# CabInst.net
KiCad netlist of a schematic drawn in EAGLE
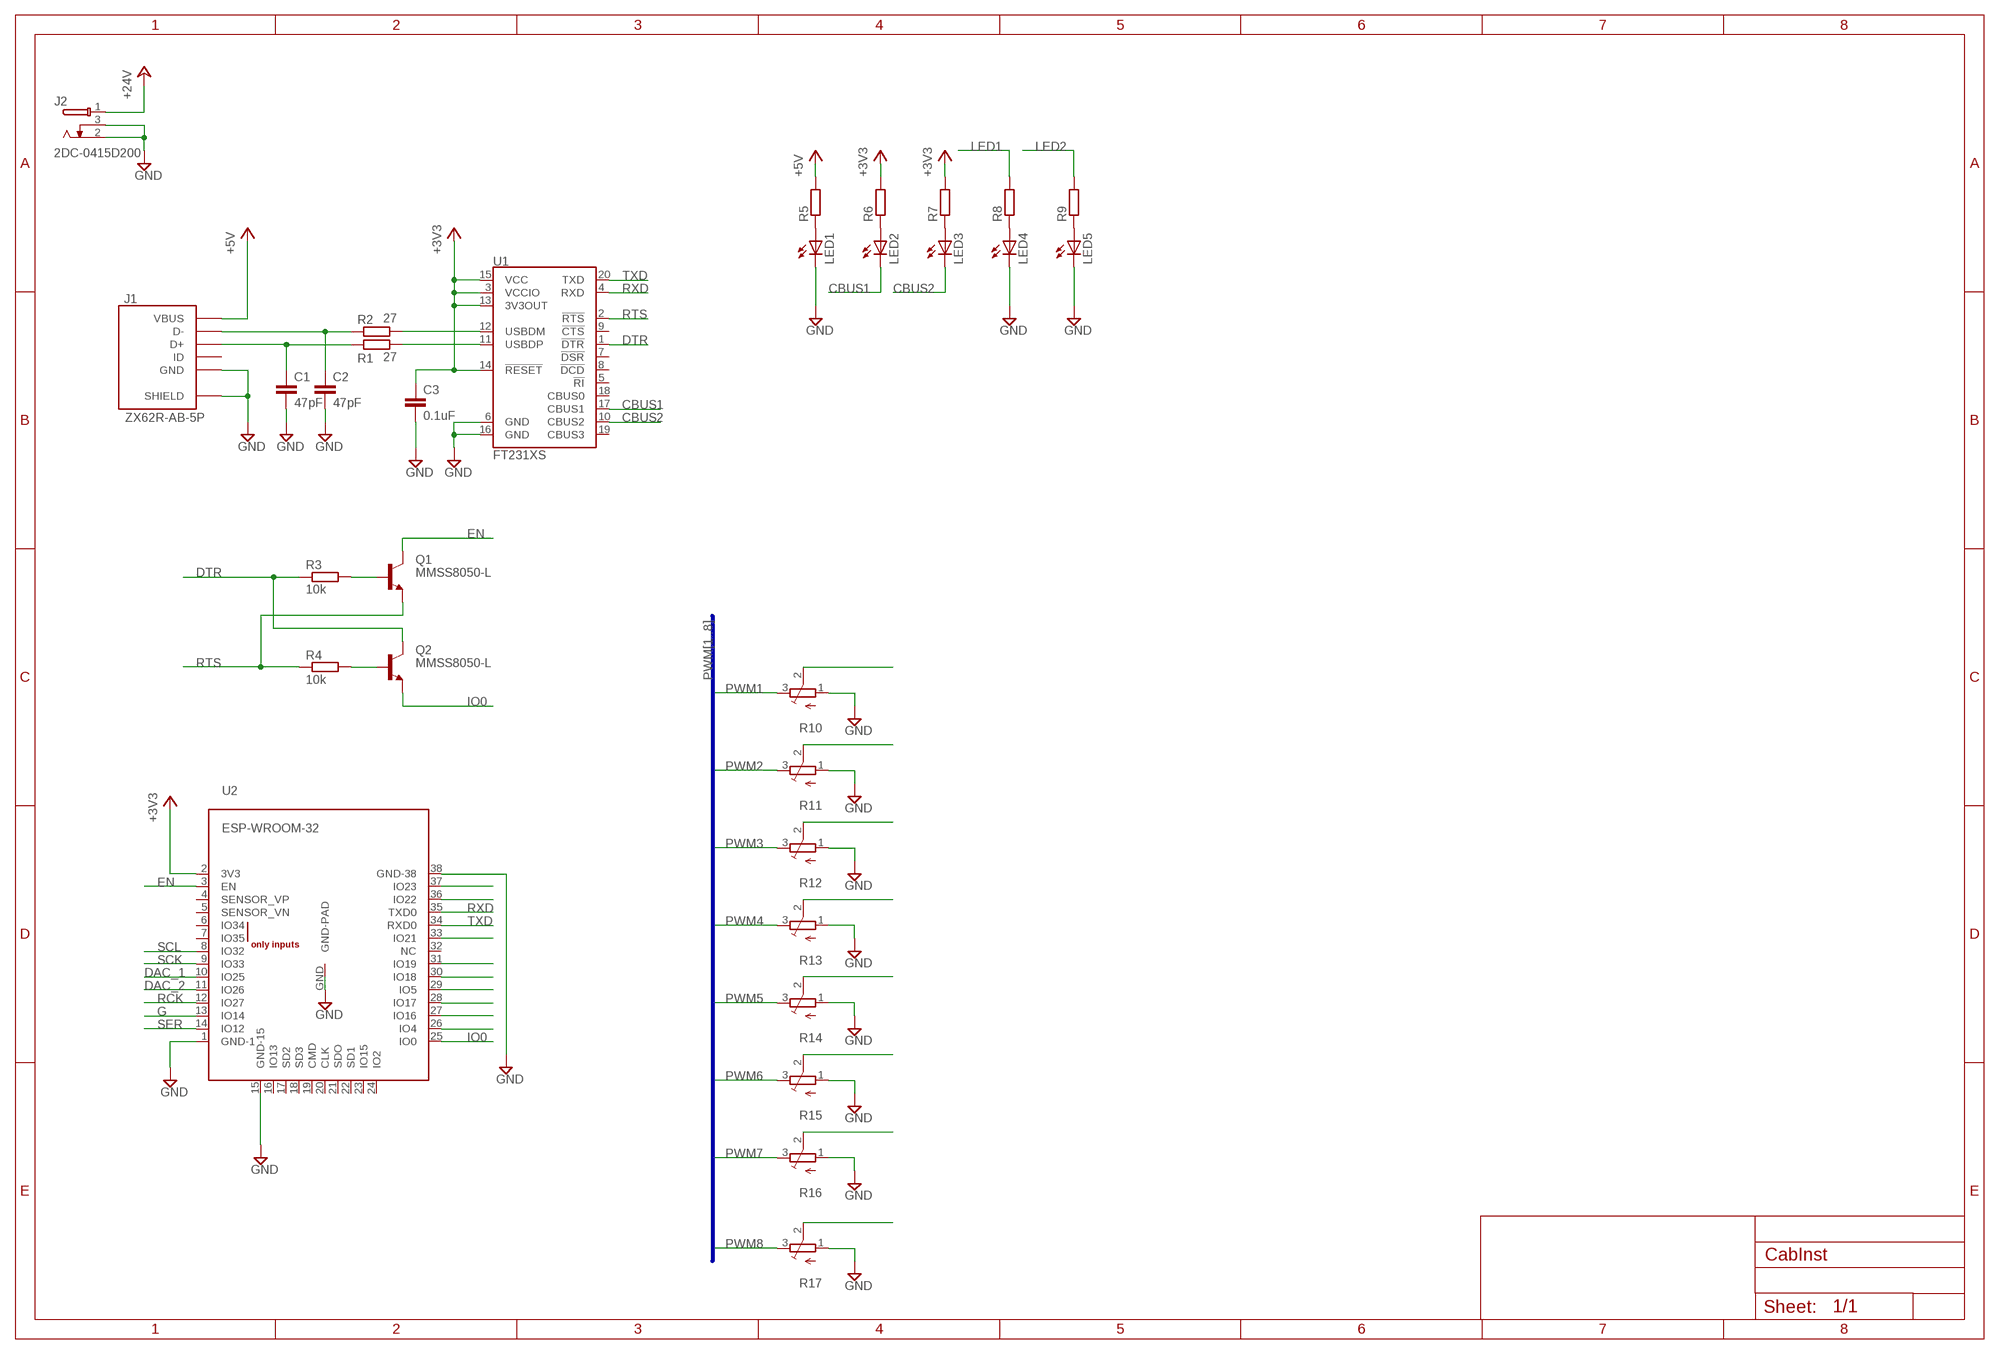
[diagram p0: schematic, sheet 1]

(export (version "E")
  (design (tool "Eeschema 10.0.6"))
  (components
    (comp (ref "C1")
      (value "47pF")
      (footprint "eagle-import:C0603")
      (libsource (lib "eagle-import") (part "C-EUC0603"))
    )
    (comp (ref "C2")
      (value "47pF")
      (footprint "eagle-import:C0603")
      (libsource (lib "eagle-import") (part "C-EUC0603"))
    )
    (comp (ref "C3")
      (value "0.1uF")
      (footprint "eagle-import:C0603")
      (libsource (lib "eagle-import") (part "C-EUC0603"))
    )
    (comp (ref "J1")
      (value "ZX62R-AB-5P")
      (footprint "eagle-import:ZX62R-B-5PA")
      (libsource (lib "eagle-import") (part "ZX62R-AB-5P"))
    )
    (comp (ref "J2")
      (value "2DC-0415D200")
      (footprint "eagle-import:2DC-0415D200")
      (libsource (lib "eagle-import") (part "2DC-0415D200"))
    )
    (comp (ref "LED1")
      (value "LEDCHIP-LED0603")
      (footprint "eagle-import:CHIP-LED0603")
      (libsource (lib "eagle-import") (part "LEDCHIP-LED0603"))
    )
    (comp (ref "LED2")
      (value "LEDCHIP-LED0603")
      (footprint "eagle-import:CHIP-LED0603")
      (libsource (lib "eagle-import") (part "LEDCHIP-LED0603"))
    )
    (comp (ref "LED3")
      (value "LEDCHIP-LED0603")
      (footprint "eagle-import:CHIP-LED0603")
      (libsource (lib "eagle-import") (part "LEDCHIP-LED0603"))
    )
    (comp (ref "LED4")
      (value "LEDCHIP-LED0603")
      (footprint "eagle-import:CHIP-LED0603")
      (libsource (lib "eagle-import") (part "LEDCHIP-LED0603"))
    )
    (comp (ref "LED5")
      (value "LEDCHIP-LED0603")
      (footprint "eagle-import:CHIP-LED0603")
      (libsource (lib "eagle-import") (part "LEDCHIP-LED0603"))
    )
    (comp (ref "Q1")
      (value "MMSS8050-L")
      (footprint "eagle-import:SOT23")
      (libsource (lib "eagle-import") (part "MMSS8050-L"))
    )
    (comp (ref "Q2")
      (value "MMSS8050-L")
      (footprint "eagle-import:SOT23")
      (libsource (lib "eagle-import") (part "MMSS8050-L"))
    )
    (comp (ref "R1")
      (value "27")
      (footprint "eagle-import:R0603")
      (libsource (lib "eagle-import") (part "R-EU_R0603"))
    )
    (comp (ref "R2")
      (value "27")
      (footprint "eagle-import:R0603")
      (libsource (lib "eagle-import") (part "R-EU_R0603"))
    )
    (comp (ref "R3")
      (value "10k")
      (footprint "eagle-import:R0603")
      (libsource (lib "eagle-import") (part "R-EU_R0603"))
    )
    (comp (ref "R4")
      (value "10k")
      (footprint "eagle-import:R0603")
      (libsource (lib "eagle-import") (part "R-EU_R0603"))
    )
    (comp (ref "R5")
      (value "R-EU_R0603")
      (footprint "eagle-import:R0603")
      (libsource (lib "eagle-import") (part "R-EU_R0603"))
    )
    (comp (ref "R6")
      (value "R-EU_R0603")
      (footprint "eagle-import:R0603")
      (libsource (lib "eagle-import") (part "R-EU_R0603"))
    )
    (comp (ref "R7")
      (value "R-EU_R0603")
      (footprint "eagle-import:R0603")
      (libsource (lib "eagle-import") (part "R-EU_R0603"))
    )
    (comp (ref "R8")
      (value "R-EU_R0603")
      (footprint "eagle-import:R0603")
      (libsource (lib "eagle-import") (part "R-EU_R0603"))
    )
    (comp (ref "R9")
      (value "R-EU_R0603")
      (footprint "eagle-import:R0603")
      (libsource (lib "eagle-import") (part "R-EU_R0603"))
    )
    (comp (ref "R10")
      (value "TRIM_EU-SM-42/43A")
      (footprint "eagle-import:SM-42_43A")
      (libsource (lib "eagle-import") (part "TRIM_EU-SM-42/43A"))
    )
    (comp (ref "R11")
      (value "TRIM_EU-SM-42/43A")
      (footprint "eagle-import:SM-42_43A")
      (libsource (lib "eagle-import") (part "TRIM_EU-SM-42/43A"))
    )
    (comp (ref "R12")
      (value "TRIM_EU-SM-42/43A")
      (footprint "eagle-import:SM-42_43A")
      (libsource (lib "eagle-import") (part "TRIM_EU-SM-42/43A"))
    )
    (comp (ref "R13")
      (value "TRIM_EU-SM-42/43A")
      (footprint "eagle-import:SM-42_43A")
      (libsource (lib "eagle-import") (part "TRIM_EU-SM-42/43A"))
    )
    (comp (ref "R14")
      (value "TRIM_EU-SM-42/43A")
      (footprint "eagle-import:SM-42_43A")
      (libsource (lib "eagle-import") (part "TRIM_EU-SM-42/43A"))
    )
    (comp (ref "R15")
      (value "TRIM_EU-SM-42/43A")
      (footprint "eagle-import:SM-42_43A")
      (libsource (lib "eagle-import") (part "TRIM_EU-SM-42/43A"))
    )
    (comp (ref "R16")
      (value "TRIM_EU-SM-42/43A")
      (footprint "eagle-import:SM-42_43A")
      (libsource (lib "eagle-import") (part "TRIM_EU-SM-42/43A"))
    )
    (comp (ref "R17")
      (value "TRIM_EU-SM-42/43A")
      (footprint "eagle-import:SM-42_43A")
      (libsource (lib "eagle-import") (part "TRIM_EU-SM-42/43A"))
    )
    (comp (ref "U1")
      (value "FT231XS")
      (footprint "eagle-import:SSOP20_L")
      (libsource (lib "eagle-import") (part "FT231XS"))
    )
    (comp (ref "U2")
      (value "ESP-WROOM-32")
      (footprint "eagle-import:ESP-WROOM-32")
      (libsource (lib "eagle-import") (part "ESP-WROOM-32"))
    )
  )
  (nets
    (net (code "1") (name "+3V3") (class "Default")
      (node (ref "C3") (pin "1") (pinfunction "1_1") (pintype "passive"))
      (node (ref "R6") (pin "2") (pinfunction "2_2") (pintype "passive"))
      (node (ref "R7") (pin "2") (pinfunction "2_2") (pintype "passive"))
      (node (ref "U1") (pin "13") (pinfunction "3V3OUT_13") (pintype "bidirectional"))
      (node (ref "U1") (pin "14") (pinfunction "~{RESET}_14") (pintype "bidirectional"))
      (node (ref "U1") (pin "15") (pinfunction "VCC_15") (pintype "bidirectional"))
      (node (ref "U1") (pin "3") (pinfunction "VCCIO_3") (pintype "bidirectional"))
      (node (ref "U2") (pin "2") (pinfunction "3V3_2") (pintype "bidirectional"))
    )
    (net (code "2") (name "+5V") (class "Default")
      (node (ref "J1") (pin "VCC") (pinfunction "VBUS_VCC") (pintype "bidirectional"))
      (node (ref "R5") (pin "2") (pinfunction "2_2") (pintype "passive"))
    )
    (net (code "3") (name "+24V") (class "Default")
      (node (ref "J2") (pin "1") (pinfunction "1_1") (pintype "passive"))
    )
    (net (code "4") (name "/CBUS1") (class "Default")
      (node (ref "LED2") (pin "C") (pinfunction "C_C") (pintype "passive"))
      (node (ref "U1") (pin "17") (pinfunction "CBUS1_17") (pintype "bidirectional"))
    )
    (net (code "5") (name "/CBUS2") (class "Default")
      (node (ref "LED3") (pin "C") (pinfunction "C_C") (pintype "passive"))
      (node (ref "U1") (pin "10") (pinfunction "CBUS2_10") (pintype "bidirectional"))
    )
    (net (code "6") (name "/DAC_1") (class "Default")
      (node (ref "U2") (pin "10") (pinfunction "IO25_10") (pintype "bidirectional"))
    )
    (net (code "7") (name "/DAC_2") (class "Default")
      (node (ref "U2") (pin "11") (pinfunction "IO26_11") (pintype "bidirectional"))
    )
    (net (code "8") (name "/DTR") (class "Default")
      (node (ref "Q2") (pin "C") (pinfunction "C_C") (pintype "passive"))
      (node (ref "R3") (pin "1") (pinfunction "1_1") (pintype "passive"))
      (node (ref "U1") (pin "1") (pinfunction "~{DTR}_1") (pintype "bidirectional"))
    )
    (net (code "9") (name "/EN") (class "Default")
      (node (ref "Q1") (pin "C") (pinfunction "C_C") (pintype "passive"))
      (node (ref "U2") (pin "3") (pinfunction "EN_3") (pintype "bidirectional"))
    )
    (net (code "10") (name "/G") (class "Default")
      (node (ref "U2") (pin "13") (pinfunction "IO14_13") (pintype "bidirectional"))
    )
    (net (code "11") (name "/IO0") (class "Default")
      (node (ref "Q2") (pin "E") (pinfunction "E_E") (pintype "passive"))
      (node (ref "U2") (pin "25") (pinfunction "IO0_25") (pintype "bidirectional"))
    )
    (net (code "12") (name "/LED1") (class "Default")
      (node (ref "R8") (pin "2") (pinfunction "2_2") (pintype "passive"))
    )
    (net (code "13") (name "/LED2") (class "Default")
      (node (ref "R9") (pin "2") (pinfunction "2_2") (pintype "passive"))
    )
    (net (code "14") (name "/PWM1") (class "Default")
      (node (ref "R10") (pin "3") (pinfunction "E_3") (pintype "passive"))
    )
    (net (code "15") (name "/PWM2") (class "Default")
      (node (ref "R11") (pin "3") (pinfunction "E_3") (pintype "passive"))
    )
    (net (code "16") (name "/PWM3") (class "Default")
      (node (ref "R12") (pin "3") (pinfunction "E_3") (pintype "passive"))
    )
    (net (code "17") (name "/PWM4") (class "Default")
      (node (ref "R13") (pin "3") (pinfunction "E_3") (pintype "passive"))
    )
    (net (code "18") (name "/PWM5") (class "Default")
      (node (ref "R14") (pin "3") (pinfunction "E_3") (pintype "passive"))
    )
    (net (code "19") (name "/PWM6") (class "Default")
      (node (ref "R15") (pin "3") (pinfunction "E_3") (pintype "passive"))
    )
    (net (code "20") (name "/PWM7") (class "Default")
      (node (ref "R16") (pin "3") (pinfunction "E_3") (pintype "passive"))
    )
    (net (code "21") (name "/PWM8") (class "Default")
      (node (ref "R17") (pin "3") (pinfunction "E_3") (pintype "passive"))
    )
    (net (code "23") (name "/RCK") (class "Default")
      (node (ref "U2") (pin "12") (pinfunction "IO27_12") (pintype "bidirectional"))
    )
    (net (code "24") (name "/RTS") (class "Default")
      (node (ref "Q1") (pin "E") (pinfunction "E_E") (pintype "passive"))
      (node (ref "R4") (pin "1") (pinfunction "1_1") (pintype "passive"))
      (node (ref "U1") (pin "2") (pinfunction "~{RTS}_2") (pintype "bidirectional"))
    )
    (net (code "25") (name "/RXD") (class "Default")
      (node (ref "U1") (pin "4") (pinfunction "RXD_4") (pintype "bidirectional"))
      (node (ref "U2") (pin "35") (pinfunction "TXD0_35") (pintype "bidirectional"))
    )
    (net (code "26") (name "/SCK") (class "Default")
      (node (ref "U2") (pin "9") (pinfunction "IO33_9") (pintype "bidirectional"))
    )
    (net (code "27") (name "/SCL") (class "Default")
      (node (ref "U2") (pin "8") (pinfunction "IO32_8") (pintype "bidirectional"))
    )
    (net (code "28") (name "/SER") (class "Default")
      (node (ref "U2") (pin "14") (pinfunction "IO12_14") (pintype "bidirectional"))
    )
    (net (code "29") (name "/TXD") (class "Default")
      (node (ref "U1") (pin "20") (pinfunction "TXD_20") (pintype "bidirectional"))
      (node (ref "U2") (pin "34") (pinfunction "RXD0_34") (pintype "bidirectional"))
    )
    (net (code "30") (name "GND") (class "Default")
      (node (ref "C1") (pin "2") (pinfunction "2_2") (pintype "passive"))
      (node (ref "C2") (pin "2") (pinfunction "2_2") (pintype "passive"))
      (node (ref "C3") (pin "2") (pinfunction "2_2") (pintype "passive"))
      (node (ref "J1") (pin "GND") (pinfunction "GND_GND") (pintype "bidirectional"))
      (node (ref "J1") (pin "SHIELD@1") (pinfunction "SHIELD_SHIELD@1") (pintype "bidirectional"))
      (node (ref "J1") (pin "SHIELD@2") (pinfunction "SHIELD_SHIELD@2") (pintype "bidirectional"))
      (node (ref "J1") (pin "SHIELD@3") (pinfunction "SHIELD_SHIELD@3") (pintype "bidirectional"))
      (node (ref "J1") (pin "SHIELD@4") (pinfunction "SHIELD_SHIELD@4") (pintype "bidirectional"))
      (node (ref "J2") (pin "2") (pinfunction "2_2") (pintype "passive"))
      (node (ref "J2") (pin "3") (pinfunction "3_3") (pintype "passive"))
      (node (ref "LED1") (pin "C") (pinfunction "C_C") (pintype "passive"))
      (node (ref "LED4") (pin "C") (pinfunction "C_C") (pintype "passive"))
      (node (ref "LED5") (pin "C") (pinfunction "C_C") (pintype "passive"))
      (node (ref "R10") (pin "1") (pinfunction "A_1") (pintype "passive"))
      (node (ref "R11") (pin "1") (pinfunction "A_1") (pintype "passive"))
      (node (ref "R12") (pin "1") (pinfunction "A_1") (pintype "passive"))
      (node (ref "R13") (pin "1") (pinfunction "A_1") (pintype "passive"))
      (node (ref "R14") (pin "1") (pinfunction "A_1") (pintype "passive"))
      (node (ref "R15") (pin "1") (pinfunction "A_1") (pintype "passive"))
      (node (ref "R16") (pin "1") (pinfunction "A_1") (pintype "passive"))
      (node (ref "R17") (pin "1") (pinfunction "A_1") (pintype "passive"))
      (node (ref "U1") (pin "16") (pinfunction "GND_16") (pintype "bidirectional"))
      (node (ref "U1") (pin "6") (pinfunction "GND_6") (pintype "bidirectional"))
      (node (ref "U2") (pin "1") (pinfunction "GND-1_1") (pintype "bidirectional"))
      (node (ref "U2") (pin "15") (pinfunction "GND-15_15") (pintype "bidirectional"))
      (node (ref "U2") (pin "38") (pinfunction "GND-38_38") (pintype "bidirectional"))
      (node (ref "U2") (pin "GND") (pinfunction "GND-PAD_GND") (pintype "bidirectional"))
    )
    (net (code "31") (name "Net-(C1-Pad1)") (class "Default")
      (node (ref "C1") (pin "1") (pinfunction "1_1") (pintype "passive"))
      (node (ref "J1") (pin "D+") (pinfunction "D+_D+") (pintype "bidirectional"))
      (node (ref "R1") (pin "1") (pinfunction "1_1") (pintype "passive"))
    )
    (net (code "32") (name "Net-(C2-Pad1)") (class "Default")
      (node (ref "C2") (pin "1") (pinfunction "1_1") (pintype "passive"))
      (node (ref "J1") (pin "D-") (pinfunction "D-_D-") (pintype "bidirectional"))
      (node (ref "R2") (pin "1") (pinfunction "1_1") (pintype "passive"))
    )
    (net (code "33") (name "Net-(LED1-PadA)") (class "Default")
      (node (ref "LED1") (pin "A") (pinfunction "A_A") (pintype "passive"))
      (node (ref "R5") (pin "1") (pinfunction "1_1") (pintype "passive"))
    )
    (net (code "34") (name "Net-(LED2-PadA)") (class "Default")
      (node (ref "LED2") (pin "A") (pinfunction "A_A") (pintype "passive"))
      (node (ref "R6") (pin "1") (pinfunction "1_1") (pintype "passive"))
    )
    (net (code "35") (name "Net-(LED3-PadA)") (class "Default")
      (node (ref "LED3") (pin "A") (pinfunction "A_A") (pintype "passive"))
      (node (ref "R7") (pin "1") (pinfunction "1_1") (pintype "passive"))
    )
    (net (code "36") (name "Net-(LED4-PadA)") (class "Default")
      (node (ref "LED4") (pin "A") (pinfunction "A_A") (pintype "passive"))
      (node (ref "R8") (pin "1") (pinfunction "1_1") (pintype "passive"))
    )
    (net (code "37") (name "Net-(LED5-PadA)") (class "Default")
      (node (ref "LED5") (pin "A") (pinfunction "A_A") (pintype "passive"))
      (node (ref "R9") (pin "1") (pinfunction "1_1") (pintype "passive"))
    )
    (net (code "38") (name "Net-(Q1-PadB)") (class "Default")
      (node (ref "Q1") (pin "B") (pinfunction "B_B") (pintype "passive"))
      (node (ref "R3") (pin "2") (pinfunction "2_2") (pintype "passive"))
    )
    (net (code "39") (name "Net-(Q2-PadB)") (class "Default")
      (node (ref "Q2") (pin "B") (pinfunction "B_B") (pintype "passive"))
      (node (ref "R4") (pin "2") (pinfunction "2_2") (pintype "passive"))
    )
    (net (code "40") (name "Net-(U1-USBDM)") (class "Default")
      (node (ref "R2") (pin "2") (pinfunction "2_2") (pintype "passive"))
      (node (ref "U1") (pin "12") (pinfunction "USBDM_12") (pintype "bidirectional"))
    )
    (net (code "41") (name "Net-(U1-USBDP)") (class "Default")
      (node (ref "R1") (pin "2") (pinfunction "2_2") (pintype "passive"))
      (node (ref "U1") (pin "11") (pinfunction "USBDP_11") (pintype "bidirectional"))
    )
    (net (code "42") (name "unconnected-(J1-PadID)") (class "Default")
      (node (ref "J1") (pin "ID") (pinfunction "ID_ID") (pintype "bidirectional"))
    )
    (net (code "43") (name "unconnected-(R10-S-Pad2)") (class "Default")
      (node (ref "R10") (pin "2") (pinfunction "S_2") (pintype "passive"))
    )
    (net (code "44") (name "unconnected-(R11-S-Pad2)") (class "Default")
      (node (ref "R11") (pin "2") (pinfunction "S_2") (pintype "passive"))
    )
    (net (code "45") (name "unconnected-(R12-S-Pad2)") (class "Default")
      (node (ref "R12") (pin "2") (pinfunction "S_2") (pintype "passive"))
    )
    (net (code "46") (name "unconnected-(R13-S-Pad2)") (class "Default")
      (node (ref "R13") (pin "2") (pinfunction "S_2") (pintype "passive"))
    )
    (net (code "47") (name "unconnected-(R14-S-Pad2)") (class "Default")
      (node (ref "R14") (pin "2") (pinfunction "S_2") (pintype "passive"))
    )
    (net (code "48") (name "unconnected-(R15-S-Pad2)") (class "Default")
      (node (ref "R15") (pin "2") (pinfunction "S_2") (pintype "passive"))
    )
    (net (code "49") (name "unconnected-(R16-S-Pad2)") (class "Default")
      (node (ref "R16") (pin "2") (pinfunction "S_2") (pintype "passive"))
    )
    (net (code "50") (name "unconnected-(R17-S-Pad2)") (class "Default")
      (node (ref "R17") (pin "2") (pinfunction "S_2") (pintype "passive"))
    )
    (net (code "51") (name "unconnected-(U1-CBUS0-Pad18)") (class "Default")
      (node (ref "U1") (pin "18") (pinfunction "CBUS0_18") (pintype "bidirectional"))
    )
    (net (code "52") (name "unconnected-(U1-CBUS3-Pad19)") (class "Default")
      (node (ref "U1") (pin "19") (pinfunction "CBUS3_19") (pintype "bidirectional"))
    )
    (net (code "53") (name "unconnected-(U1-~{CTS}-Pad9)") (class "Default")
      (node (ref "U1") (pin "9") (pinfunction "~{CTS}_9") (pintype "bidirectional"))
    )
    (net (code "54") (name "unconnected-(U1-~{DCD}-Pad8)") (class "Default")
      (node (ref "U1") (pin "8") (pinfunction "~{DCD}_8") (pintype "bidirectional"))
    )
    (net (code "55") (name "unconnected-(U1-~{DSR}-Pad7)") (class "Default")
      (node (ref "U1") (pin "7") (pinfunction "~{DSR}_7") (pintype "bidirectional"))
    )
    (net (code "56") (name "unconnected-(U1-~{RI}-Pad5)") (class "Default")
      (node (ref "U1") (pin "5") (pinfunction "~{RI}_5") (pintype "bidirectional"))
    )
    (net (code "57") (name "unconnected-(U2-CLK-Pad20)") (class "Default")
      (node (ref "U2") (pin "20") (pinfunction "CLK_20") (pintype "bidirectional"))
    )
    (net (code "58") (name "unconnected-(U2-CMD-Pad19)") (class "Default")
      (node (ref "U2") (pin "19") (pinfunction "CMD_19") (pintype "bidirectional"))
    )
    (net (code "59") (name "unconnected-(U2-IO2-Pad24)") (class "Default")
      (node (ref "U2") (pin "24") (pinfunction "IO2_24") (pintype "bidirectional"))
    )
    (net (code "60") (name "unconnected-(U2-IO4-Pad26)") (class "Default")
      (node (ref "U2") (pin "26") (pinfunction "IO4_26") (pintype "bidirectional"))
    )
    (net (code "61") (name "unconnected-(U2-IO5-Pad29)") (class "Default")
      (node (ref "U2") (pin "29") (pinfunction "IO5_29") (pintype "bidirectional"))
    )
    (net (code "62") (name "unconnected-(U2-IO13-Pad16)") (class "Default")
      (node (ref "U2") (pin "16") (pinfunction "IO13_16") (pintype "bidirectional"))
    )
    (net (code "63") (name "unconnected-(U2-IO15-Pad23)") (class "Default")
      (node (ref "U2") (pin "23") (pinfunction "IO15_23") (pintype "bidirectional"))
    )
    (net (code "64") (name "unconnected-(U2-IO16-Pad27)") (class "Default")
      (node (ref "U2") (pin "27") (pinfunction "IO16_27") (pintype "bidirectional"))
    )
    (net (code "65") (name "unconnected-(U2-IO17-Pad28)") (class "Default")
      (node (ref "U2") (pin "28") (pinfunction "IO17_28") (pintype "bidirectional"))
    )
    (net (code "66") (name "unconnected-(U2-IO18-Pad30)") (class "Default")
      (node (ref "U2") (pin "30") (pinfunction "IO18_30") (pintype "bidirectional"))
    )
    (net (code "67") (name "unconnected-(U2-IO19-Pad31)") (class "Default")
      (node (ref "U2") (pin "31") (pinfunction "IO19_31") (pintype "bidirectional"))
    )
    (net (code "68") (name "unconnected-(U2-IO21-Pad33)") (class "Default")
      (node (ref "U2") (pin "33") (pinfunction "IO21_33") (pintype "bidirectional"))
    )
    (net (code "69") (name "unconnected-(U2-IO22-Pad36)") (class "Default")
      (node (ref "U2") (pin "36") (pinfunction "IO22_36") (pintype "bidirectional"))
    )
    (net (code "70") (name "unconnected-(U2-IO23-Pad37)") (class "Default")
      (node (ref "U2") (pin "37") (pinfunction "IO23_37") (pintype "bidirectional"))
    )
    (net (code "71") (name "unconnected-(U2-IO34-Pad6)") (class "Default")
      (node (ref "U2") (pin "6") (pinfunction "IO34_6") (pintype "input"))
    )
    (net (code "72") (name "unconnected-(U2-IO35-Pad7)") (class "Default")
      (node (ref "U2") (pin "7") (pinfunction "IO35_7") (pintype "input"))
    )
    (net (code "73") (name "unconnected-(U2-NC-Pad32)") (class "Default")
      (node (ref "U2") (pin "32") (pinfunction "NC_32") (pintype "bidirectional"))
    )
    (net (code "74") (name "unconnected-(U2-SD1-Pad22)") (class "Default")
      (node (ref "U2") (pin "22") (pinfunction "SD1_22") (pintype "bidirectional"))
    )
    (net (code "75") (name "unconnected-(U2-SD2-Pad17)") (class "Default")
      (node (ref "U2") (pin "17") (pinfunction "SD2_17") (pintype "bidirectional"))
    )
    (net (code "76") (name "unconnected-(U2-SD3-Pad18)") (class "Default")
      (node (ref "U2") (pin "18") (pinfunction "SD3_18") (pintype "bidirectional"))
    )
    (net (code "77") (name "unconnected-(U2-SDO-Pad21)") (class "Default")
      (node (ref "U2") (pin "21") (pinfunction "SDO_21") (pintype "bidirectional"))
    )
    (net (code "78") (name "unconnected-(U2-SENSOR_VN-Pad5)") (class "Default")
      (node (ref "U2") (pin "5") (pinfunction "SENSOR_VN_5") (pintype "input"))
    )
    (net (code "79") (name "unconnected-(U2-SENSOR_VP-Pad4)") (class "Default")
      (node (ref "U2") (pin "4") (pinfunction "SENSOR_VP_4") (pintype "input"))
    )
  )
)
